# Attenuator_Proto.net
KiCad netlist of a schematic drawn in Altium Designer
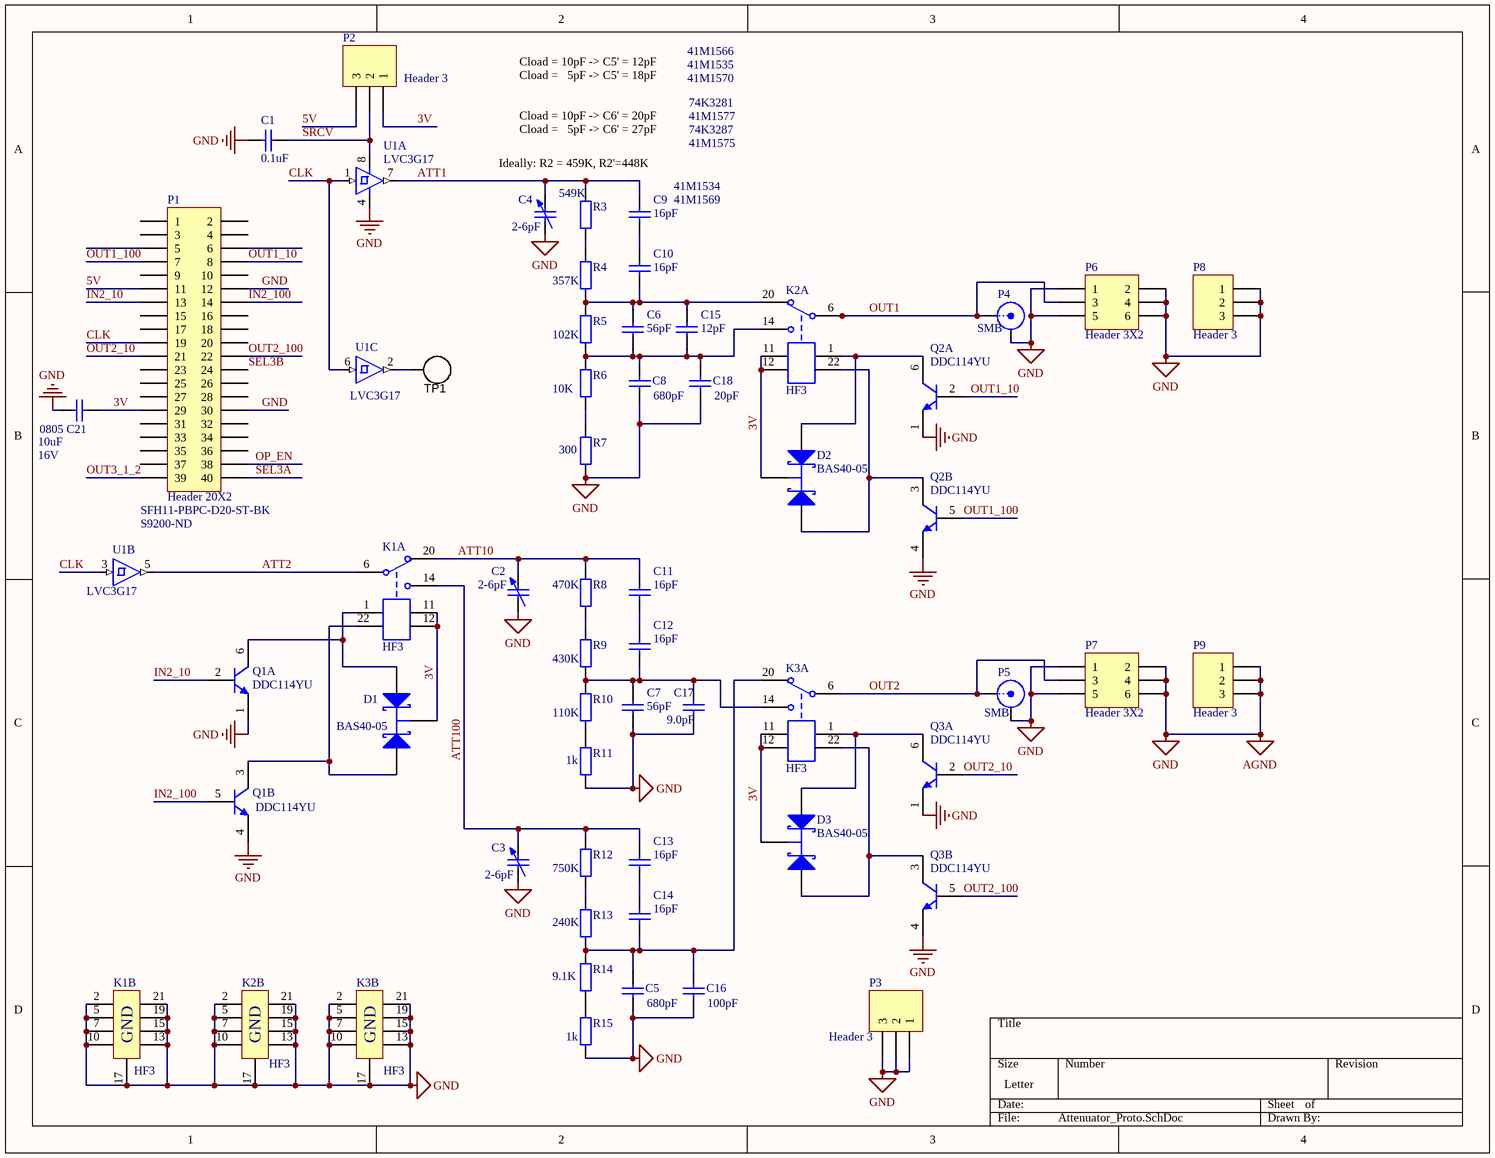
[diagram p0: Attenuator_Proto.SchDoc]

(export (version "E")
  (design (tool "Eeschema 10.0.6"))
  (components
    (comp (ref "C1")
      (value "0.1uF")
      (footprint "C0805")
      (description "Capacitor")
      (fields (field (name "Comment") "Cap") (field (name "PUBLISHER") "Altium Limited"))
      (libsource (lib "Miscellaneous Devices") (part "Cap"))
    )
    (comp (ref "C2")
      (value "2-6pF")
      (footprint "CAPC3225N")
      (description "Variable or Adjustable Capacitor")
      (fields (field (name "Comment") "Cap Var") (field (name "PUBLISHER") "Altium Limited"))
      (libsource (lib "Miscellaneous Devices") (part "Cap Var"))
    )
    (comp (ref "C3")
      (value "2-6pF")
      (footprint "CAPC3225N")
      (description "Variable or Adjustable Capacitor")
      (fields (field (name "Comment") "Cap Var") (field (name "PUBLISHER") "Altium Limited"))
      (libsource (lib "Miscellaneous Devices") (part "Cap Var"))
    )
    (comp (ref "C4")
      (value "2-6pF")
      (footprint "CAPC3225N")
      (description "Variable or Adjustable Capacitor")
      (fields (field (name "Comment") "Cap Var") (field (name "PUBLISHER") "Altium Limited"))
      (libsource (lib "Miscellaneous Devices") (part "Cap Var"))
    )
    (comp (ref "C5")
      (value "680pF")
      (footprint "c0805")
      (description "Capacitor")
      (fields (field (name "Comment") "Cap") (field (name "PUBLISHER") "Altium Limited"))
      (libsource (lib "Miscellaneous Devices") (part "Cap"))
    )
    (comp (ref "C6")
      (value "56pF")
      (footprint "c0805")
      (description "Capacitor")
      (fields (field (name "Comment") "Cap") (field (name "PUBLISHER") "Altium Limited"))
      (libsource (lib "Miscellaneous Devices") (part "Cap"))
    )
    (comp (ref "C7")
      (value "56pF")
      (footprint "c0805")
      (description "Capacitor")
      (fields (field (name "Comment") "Cap") (field (name "PUBLISHER") "Altium Limited"))
      (libsource (lib "Miscellaneous Devices") (part "Cap"))
    )
    (comp (ref "C8")
      (value "680pF")
      (footprint "c0805")
      (description "Capacitor")
      (fields (field (name "Comment") "Cap") (field (name "PUBLISHER") "Altium Limited"))
      (libsource (lib "Miscellaneous Devices") (part "Cap"))
    )
    (comp (ref "C9")
      (value "16pF")
      (footprint "c0805")
      (description "Capacitor")
      (fields
        (field (name "SUPPLIER PART NUMBER 1") "41M1569")
        (field (name "SUPPLIER PART NUMBER 2") "41M1534")
        (field (name "Comment") "Cap")
        (field (name "PUBLISHER") "Altium Limited")
      )
      (libsource (lib "Miscellaneous Devices") (part "Cap"))
    )
    (comp (ref "C10")
      (value "16pF")
      (footprint "c0805")
      (description "Capacitor")
      (fields (field (name "Comment") "Cap") (field (name "PUBLISHER") "Altium Limited"))
      (libsource (lib "Miscellaneous Devices") (part "Cap"))
    )
    (comp (ref "C11")
      (value "16pF")
      (footprint "c0805")
      (description "Capacitor")
      (fields (field (name "Comment") "Cap") (field (name "PUBLISHER") "Altium Limited"))
      (libsource (lib "Miscellaneous Devices") (part "Cap"))
    )
    (comp (ref "C12")
      (value "16pF")
      (footprint "c0805")
      (description "Capacitor")
      (fields (field (name "Comment") "Cap") (field (name "PUBLISHER") "Altium Limited"))
      (libsource (lib "Miscellaneous Devices") (part "Cap"))
    )
    (comp (ref "C13")
      (value "16pF")
      (footprint "c0805")
      (description "Capacitor")
      (fields (field (name "Comment") "Cap") (field (name "PUBLISHER") "Altium Limited"))
      (libsource (lib "Miscellaneous Devices") (part "Cap"))
    )
    (comp (ref "C14")
      (value "16pF")
      (footprint "c0805")
      (description "Capacitor")
      (fields (field (name "Comment") "Cap") (field (name "PUBLISHER") "Altium Limited"))
      (libsource (lib "Miscellaneous Devices") (part "Cap"))
    )
    (comp (ref "C15")
      (value "12pF")
      (footprint "c0805")
      (description "Capacitor")
      (fields
        (field (name "SUPPLIER PART NUMBER 2") "41M1570")
        (field (name "SUPPLIER PART NUMBER 1") "41M1535")
        (field (name "SUPPLIER PART NUMBER 3") "41M1566")
        (field (name "Comment") "Cap")
        (field (name "PUBLISHER") "Altium Limited")
      )
      (libsource (lib "Miscellaneous Devices") (part "Cap"))
    )
    (comp (ref "C16")
      (value "100pF")
      (footprint "c0805")
      (description "Capacitor")
      (fields (field (name "Comment") "Cap") (field (name "PUBLISHER") "Altium Limited"))
      (libsource (lib "Miscellaneous Devices") (part "Cap"))
    )
    (comp (ref "C17")
      (value "9.0pF")
      (footprint "c0805")
      (description "Capacitor")
      (fields (field (name "Comment") "Cap") (field (name "PUBLISHER") "Altium Limited"))
      (libsource (lib "Miscellaneous Devices") (part "Cap"))
    )
    (comp (ref "C18")
      (value "20pF")
      (footprint "c0805")
      (description "Capacitor")
      (fields
        (field (name "SUPPLIER PART NUMBER 1") "41M1575")
        (field (name "SUPPLIER PART NUMBER 2") "74K3287")
        (field (name "SUPPLIER PART NUMBER 3") "41M1577")
        (field (name "SUPPLIER PART NUMBER 4") "74K3281")
        (field (name "Comment") "Cap")
        (field (name "PUBLISHER") "Altium Limited")
      )
      (libsource (lib "Miscellaneous Devices") (part "Cap"))
    )
    (comp (ref "C21")
      (value "10uF")
      (footprint "CAPC2512L")
      (description "Capacitor (Semiconductor SIM Model)")
      (fields
        (field (name "PACKAGEREFERENCE") "0805")
        (field (name "VOLTAGE") "16V")
        (field (name "MANUFACTURER") "Murata")
        (field (name "PARTNUMBER") "GRM21BF51C106ZE15L")
        (field (name "PUBLISHER") "Altium Limited")
      )
      (libsource (lib "Miscellaneous Devices") (part "Cap Semi"))
    )
    (comp (ref "D1")
      (value "BAS40-05")
      (footprint "SOT-23")
      (description "Silicon AF Schottky Diode for High-Speed Switching")
      (fields (field (name "PUBLISHER") "Altium Limited"))
      (libsource (lib "Infineon Discrete Diode") (part "BAS40-05"))
    )
    (comp (ref "D2")
      (value "BAS40-05")
      (footprint "SOT-23")
      (description "Silicon AF Schottky Diode for High-Speed Switching")
      (fields (field (name "PUBLISHER") "Altium Limited"))
      (libsource (lib "Infineon Discrete Diode") (part "BAS40-05"))
    )
    (comp (ref "D3")
      (value "BAS40-05")
      (footprint "SOT-23")
      (description "Silicon AF Schottky Diode for High-Speed Switching")
      (fields (field (name "PUBLISHER") "Altium Limited"))
      (libsource (lib "Infineon Discrete Diode") (part "BAS40-05"))
    )
    (comp (ref "K1")
      (value "HF3_2coils_latching")
      (footprint "HF3-75_Ohm")
      (description "HF3 Relay, Latching type, 2 coils")
      (fields (field (name "MANUFACTURER") "Tyco Electronics") (field (name "PARTNUMBER") "HF3"))
      (libsource (lib "") (part "HF3_2coils_latching_1"))
    )
    (comp (ref "K2")
      (value "HF3_2coils_latching")
      (footprint "HF3-75_Ohm")
      (description "HF3 Relay, Latching type, 2 coils")
      (fields (field (name "MANUFACTURER") "Tyco Electronics") (field (name "PARTNUMBER") "HF3"))
      (libsource (lib "") (part "HF3_2coils_latching_1"))
    )
    (comp (ref "K3")
      (value "HF3_2coils_latching")
      (footprint "HF3-75_Ohm")
      (description "HF3 Relay, Latching type, 2 coils")
      (fields (field (name "MANUFACTURER") "Tyco Electronics") (field (name "PARTNUMBER") "HF3"))
      (libsource (lib "") (part "HF3_2coils_latching_1"))
    )
    (comp (ref "P1")
      (value "Header 20X2")
      (footprint "HDR2X20")
      (description "Header, 20-Pin, Dual row")
      (fields
        (field (name "PARTNUMBER") "SFH11-PBPC-D20-ST-BK")
        (field (name "SUPPLIER PART NUMBER 1") "S9200-ND")
        (field (name "PUBLISHER") "Altium Limited")
      )
      (libsource (lib "Miscellaneous Connectors") (part "Header 20X2"))
    )
    (comp (ref "P2")
      (value "Header 3")
      (footprint "HDR1X3")
      (description "Header, 3-Pin")
      (fields (field (name "PUBLISHER") "Altium Limited"))
      (libsource (lib "Miscellaneous Connectors") (part "Header 3"))
    )
    (comp (ref "P3")
      (value "Header 3")
      (footprint "HDR1X3")
      (description "Header, 3-Pin")
      (fields (field (name "PUBLISHER") "Altium Limited"))
      (libsource (lib "") (part "Header 3_2"))
    )
    (comp (ref "P4")
      (value "SMB")
      (footprint "SMB_V-RJ45")
      (description "SMB Straight Connector")
      (fields (field (name "PUBLISHER") "Altium Limited"))
      (libsource (lib "Miscellaneous Connectors") (part "SMB"))
    )
    (comp (ref "P5")
      (value "SMB")
      (footprint "SMB_V-RJ45")
      (description "SMB Straight Connector")
      (fields (field (name "PUBLISHER") "Altium Limited"))
      (libsource (lib "Miscellaneous Connectors") (part "SMB"))
    )
    (comp (ref "P6")
      (value "Header 3X2")
      (footprint "HDR2X3")
      (description "Header, 3-Pin, Dual row")
      (fields (field (name "PUBLISHER") "Altium Limited"))
      (libsource (lib "Miscellaneous Connectors") (part "Header 3X2"))
    )
    (comp (ref "P7")
      (value "Header 3X2")
      (footprint "HDR2X3")
      (description "Header, 3-Pin, Dual row")
      (fields (field (name "PUBLISHER") "Altium Limited"))
      (libsource (lib "Miscellaneous Connectors") (part "Header 3X2"))
    )
    (comp (ref "P8")
      (value "Header 3")
      (footprint "HDR1X3")
      (description "Header, 3-Pin")
      (fields (field (name "PUBLISHER") "Altium Limited"))
      (libsource (lib "") (part "Header 3_1"))
    )
    (comp (ref "P9")
      (value "Header 3")
      (footprint "HDR1X3")
      (description "Header, 3-Pin")
      (fields (field (name "PUBLISHER") "Altium Limited"))
      (libsource (lib "") (part "Header 3_1"))
    )
    (comp (ref "Q1")
      (value "DDCxxxxU")
      (footprint "SOT-363")
      (description "NPN PRE-BIASED SMALL SIGNAL DUAL SURFACE MOUNT TRANSISTOR")
      (fields (field (name "PARTNUMBER") "DDC114YU"))
      (libsource (lib "iXBT") (part "DDCxxxxU"))
    )
    (comp (ref "Q2")
      (value "DDCxxxxU")
      (footprint "SOT-363")
      (description "NPN PRE-BIASED SMALL SIGNAL DUAL SURFACE MOUNT TRANSISTOR")
      (fields (field (name "PARTNUMBER") "DDC114YU"))
      (libsource (lib "iXBT") (part "DDCxxxxU"))
    )
    (comp (ref "Q3")
      (value "DDCxxxxU")
      (footprint "SOT-363")
      (description "NPN PRE-BIASED SMALL SIGNAL DUAL SURFACE MOUNT TRANSISTOR")
      (fields (field (name "PARTNUMBER") "DDC114YU"))
      (libsource (lib "iXBT") (part "DDCxxxxU"))
    )
    (comp (ref "R3")
      (value "549K")
      (footprint "0805")
      (description "Resistor")
      (fields (field (name "Comment") "Res2") (field (name "PUBLISHER") "Altium Limited"))
      (libsource (lib "Miscellaneous Devices") (part "Res2"))
    )
    (comp (ref "R4")
      (value "357K")
      (footprint "0805")
      (description "Resistor")
      (fields (field (name "Comment") "Res2") (field (name "PUBLISHER") "Altium Limited"))
      (libsource (lib "Miscellaneous Devices") (part "Res2"))
    )
    (comp (ref "R5")
      (value "102K")
      (footprint "0805")
      (description "Resistor")
      (fields (field (name "Comment") "Res2") (field (name "PUBLISHER") "Altium Limited"))
      (libsource (lib "Miscellaneous Devices") (part "Res2"))
    )
    (comp (ref "R6")
      (value "10K")
      (footprint "0805")
      (description "Resistor")
      (fields (field (name "Comment") "Res2") (field (name "PUBLISHER") "Altium Limited"))
      (libsource (lib "Miscellaneous Devices") (part "Res2"))
    )
    (comp (ref "R7")
      (value "300")
      (footprint "0805")
      (description "Resistor")
      (fields (field (name "Comment") "Res2") (field (name "PUBLISHER") "Altium Limited"))
      (libsource (lib "Miscellaneous Devices") (part "Res2"))
    )
    (comp (ref "R8")
      (value "470K")
      (footprint "0805")
      (description "Resistor")
      (fields (field (name "Comment") "Res2") (field (name "PUBLISHER") "Altium Limited"))
      (libsource (lib "Miscellaneous Devices") (part "Res2"))
    )
    (comp (ref "R9")
      (value "430K")
      (footprint "0805")
      (description "Resistor")
      (fields (field (name "Comment") "Res2") (field (name "PUBLISHER") "Altium Limited"))
      (libsource (lib "Miscellaneous Devices") (part "Res2"))
    )
    (comp (ref "R10")
      (value "110K")
      (footprint "0805")
      (description "Resistor")
      (fields (field (name "Comment") "Res2") (field (name "PUBLISHER") "Altium Limited"))
      (libsource (lib "Miscellaneous Devices") (part "Res2"))
    )
    (comp (ref "R11")
      (value "1k")
      (footprint "0805")
      (description "Resistor")
      (fields (field (name "Comment") "Res2") (field (name "PUBLISHER") "Altium Limited"))
      (libsource (lib "Miscellaneous Devices") (part "Res2"))
    )
    (comp (ref "R12")
      (value "750K")
      (footprint "0805")
      (description "Resistor")
      (fields (field (name "Comment") "Res2") (field (name "PUBLISHER") "Altium Limited"))
      (libsource (lib "Miscellaneous Devices") (part "Res2"))
    )
    (comp (ref "R13")
      (value "240K")
      (footprint "0805")
      (description "Resistor")
      (fields (field (name "Comment") "Res2") (field (name "PUBLISHER") "Altium Limited"))
      (libsource (lib "Miscellaneous Devices") (part "Res2"))
    )
    (comp (ref "R14")
      (value "9.1K")
      (footprint "0805")
      (description "Resistor")
      (fields (field (name "Comment") "Res2") (field (name "PUBLISHER") "Altium Limited"))
      (libsource (lib "Miscellaneous Devices") (part "Res2"))
    )
    (comp (ref "R15")
      (value "1k")
      (footprint "0805")
      (description "Resistor")
      (fields (field (name "Comment") "Res2") (field (name "PUBLISHER") "Altium Limited"))
      (libsource (lib "Miscellaneous Devices") (part "Res2"))
    )
    (comp (ref "TP1")
      (value "TESTPOINT")
      (footprint "TESTPOINT")
      (description "TEST POINT.  No entry in BOM.")
      (libsource (lib "NSC MiscParts") (part "TESTPOINT"))
    )
    (comp (ref "U1")
      (value "LVC3G17")
      (footprint "sm8")
      (fields
        (field (name "MANUFACTURER") "Texas Instruments")
        (field (name "MANUFACTURER PART NUMBER") "SN74LVC3G17DCTR")
      )
      (libsource (lib "VIVENG_Library") (part "SN74LVC3G17DCTR"))
    )
  )
  (nets
    (net (code "1") (name "/3V") (class "Default")
      (node (ref "C21") (pin "1") (pinfunction "1_1") (pintype "passive"))
      (node (ref "D1") (pin "3") (pinfunction "K_3") (pintype "passive"))
      (node (ref "D2") (pin "3") (pinfunction "K_3") (pintype "passive"))
      (node (ref "D3") (pin "3") (pinfunction "K_3") (pintype "passive"))
      (node (ref "K1") (pin "11") (pinfunction "11_11") (pintype "passive"))
      (node (ref "K1") (pin "12") (pinfunction "12_12") (pintype "passive"))
      (node (ref "K2") (pin "11") (pinfunction "11_11") (pintype "passive"))
      (node (ref "K2") (pin "12") (pinfunction "12_12") (pintype "passive"))
      (node (ref "K3") (pin "11") (pinfunction "11_11") (pintype "passive"))
      (node (ref "K3") (pin "12") (pinfunction "12_12") (pintype "passive"))
      (node (ref "P1") (pin "29") (pinfunction "29_29") (pintype "passive"))
      (node (ref "P2") (pin "1") (pinfunction "1_1") (pintype "passive"))
    )
    (net (code "2") (name "/5V") (class "Default")
      (node (ref "P1") (pin "11") (pinfunction "11_11") (pintype "passive"))
      (node (ref "P2") (pin "3") (pinfunction "3_3") (pintype "passive"))
    )
    (net (code "3") (name "/ATT1") (class "Default")
      (node (ref "C4") (pin "2") (pinfunction "2_2") (pintype "passive"))
      (node (ref "C9") (pin "2") (pinfunction "2_2") (pintype "passive"))
      (node (ref "R3") (pin "2") (pinfunction "2_2") (pintype "passive"))
      (node (ref "U1") (pin "7") (pinfunction "1Y_7") (pintype "output"))
    )
    (net (code "4") (name "/ATT2") (class "Default")
      (node (ref "K1") (pin "6") (pinfunction "6_6") (pintype "passive"))
      (node (ref "U1") (pin "5") (pinfunction "2Y_5") (pintype "output"))
    )
    (net (code "5") (name "/ATT10") (class "Default")
      (node (ref "C11") (pin "2") (pinfunction "2_2") (pintype "passive"))
      (node (ref "C2") (pin "2") (pinfunction "2_2") (pintype "passive"))
      (node (ref "K1") (pin "20") (pinfunction "20_20") (pintype "passive"))
      (node (ref "R8") (pin "2") (pinfunction "2_2") (pintype "passive"))
    )
    (net (code "6") (name "/ATT100") (class "Default")
      (node (ref "C13") (pin "2") (pinfunction "2_2") (pintype "passive"))
      (node (ref "C3") (pin "2") (pinfunction "2_2") (pintype "passive"))
      (node (ref "K1") (pin "14") (pinfunction "14_14") (pintype "passive"))
      (node (ref "R12") (pin "2") (pinfunction "2_2") (pintype "passive"))
    )
    (net (code "7") (name "/CLK") (class "Default")
      (node (ref "P1") (pin "19") (pinfunction "19_19") (pintype "passive"))
      (node (ref "U1") (pin "1") (pinfunction "1A_1") (pintype "input"))
      (node (ref "U1") (pin "3") (pinfunction "2A_3") (pintype "input"))
      (node (ref "U1") (pin "6") (pinfunction "3A_6") (pintype "input"))
    )
    (net (code "8") (name "/IN2_10") (class "Default")
      (node (ref "P1") (pin "13") (pinfunction "13_13") (pintype "passive"))
      (node (ref "Q1") (pin "2") (pinfunction "B_2") (pintype "passive"))
    )
    (net (code "9") (name "/IN2_100") (class "Default")
      (node (ref "P1") (pin "14") (pinfunction "14_14") (pintype "passive"))
      (node (ref "Q1") (pin "5") (pinfunction "B_5") (pintype "passive"))
    )
    (net (code "10") (name "/OP_EN") (class "Default")
      (node (ref "P1") (pin "38") (pinfunction "38_38") (pintype "passive"))
    )
    (net (code "11") (name "/OUT1") (class "Default")
      (node (ref "K2") (pin "6") (pinfunction "6_6") (pintype "passive"))
      (node (ref "P4") (pin "1") (pinfunction "X_1") (pintype "passive"))
      (node (ref "P6") (pin "3") (pinfunction "3_3") (pintype "passive"))
    )
    (net (code "12") (name "/OUT1_10") (class "Default")
      (node (ref "P1") (pin "8") (pinfunction "8_8") (pintype "passive"))
      (node (ref "Q2") (pin "2") (pinfunction "B_2") (pintype "passive"))
    )
    (net (code "13") (name "/OUT1_100") (class "Default")
      (node (ref "P1") (pin "7") (pinfunction "7_7") (pintype "passive"))
      (node (ref "Q2") (pin "5") (pinfunction "B_5") (pintype "passive"))
    )
    (net (code "14") (name "/OUT2") (class "Default")
      (node (ref "K3") (pin "6") (pinfunction "6_6") (pintype "passive"))
      (node (ref "P5") (pin "1") (pinfunction "X_1") (pintype "passive"))
      (node (ref "P7") (pin "3") (pinfunction "3_3") (pintype "passive"))
    )
    (net (code "15") (name "/OUT2_10") (class "Default")
      (node (ref "P1") (pin "21") (pinfunction "21_21") (pintype "passive"))
      (node (ref "Q3") (pin "2") (pinfunction "B_2") (pintype "passive"))
    )
    (net (code "16") (name "/OUT2_100") (class "Default")
      (node (ref "P1") (pin "22") (pinfunction "22_22") (pintype "passive"))
      (node (ref "Q3") (pin "5") (pinfunction "B_5") (pintype "passive"))
    )
    (net (code "17") (name "/OUT3_1_2") (class "Default")
      (node (ref "P1") (pin "39") (pinfunction "39_39") (pintype "passive"))
    )
    (net (code "18") (name "/SEL3A") (class "Default")
      (node (ref "P1") (pin "40") (pinfunction "40_40") (pintype "passive"))
    )
    (net (code "19") (name "/SEL3B") (class "Default")
      (node (ref "P1") (pin "24") (pinfunction "24_24") (pintype "passive"))
    )
    (net (code "20") (name "/SRCV") (class "Default")
      (node (ref "C1") (pin "1") (pinfunction "1_1") (pintype "passive"))
      (node (ref "P2") (pin "2") (pinfunction "2_2") (pintype "passive"))
      (node (ref "U1") (pin "8") (pinfunction "VCC_8") (pintype "power_in"))
    )
    (net (code "21") (name "AGND") (class "Default")
      (node (ref "C1") (pin "2") (pinfunction "2_2") (pintype "passive"))
      (node (ref "C16") (pin "1") (pinfunction "1_1") (pintype "passive"))
      (node (ref "C17") (pin "1") (pinfunction "1_1") (pintype "passive"))
      (node (ref "C18") (pin "1") (pinfunction "1_1") (pintype "passive"))
      (node (ref "C2") (pin "1") (pinfunction "1_1") (pintype "passive"))
      (node (ref "C21") (pin "2") (pinfunction "2_2") (pintype "passive"))
      (node (ref "C3") (pin "1") (pinfunction "1_1") (pintype "passive"))
      (node (ref "C4") (pin "1") (pinfunction "1_1") (pintype "passive"))
      (node (ref "C5") (pin "1") (pinfunction "1_1") (pintype "passive"))
      (node (ref "C7") (pin "1") (pinfunction "1_1") (pintype "passive"))
      (node (ref "C8") (pin "1") (pinfunction "1_1") (pintype "passive"))
      (node (ref "K1") (pin "10") (pinfunction "GND_10") (pintype "power_in"))
      (node (ref "K1") (pin "13") (pinfunction "GND_13") (pintype "power_in"))
      (node (ref "K1") (pin "15") (pinfunction "GND_15") (pintype "power_in"))
      (node (ref "K1") (pin "17") (pinfunction "GND_17") (pintype "power_in"))
      (node (ref "K1") (pin "19") (pinfunction "GND_19") (pintype "power_in"))
      (node (ref "K1") (pin "2") (pinfunction "GND_2") (pintype "power_in"))
      (node (ref "K1") (pin "21") (pinfunction "GND_21") (pintype "power_in"))
      (node (ref "K1") (pin "5") (pinfunction "GND_5") (pintype "power_in"))
      (node (ref "K1") (pin "7") (pinfunction "GND_7") (pintype "power_in"))
      (node (ref "K2") (pin "10") (pinfunction "GND_10") (pintype "power_in"))
      (node (ref "K2") (pin "13") (pinfunction "GND_13") (pintype "power_in"))
      (node (ref "K2") (pin "15") (pinfunction "GND_15") (pintype "power_in"))
      (node (ref "K2") (pin "17") (pinfunction "GND_17") (pintype "power_in"))
      (node (ref "K2") (pin "19") (pinfunction "GND_19") (pintype "power_in"))
      (node (ref "K2") (pin "2") (pinfunction "GND_2") (pintype "power_in"))
      (node (ref "K2") (pin "21") (pinfunction "GND_21") (pintype "power_in"))
      (node (ref "K2") (pin "5") (pinfunction "GND_5") (pintype "power_in"))
      (node (ref "K2") (pin "7") (pinfunction "GND_7") (pintype "power_in"))
      (node (ref "K3") (pin "10") (pinfunction "GND_10") (pintype "power_in"))
      (node (ref "K3") (pin "13") (pinfunction "GND_13") (pintype "power_in"))
      (node (ref "K3") (pin "15") (pinfunction "GND_15") (pintype "power_in"))
      (node (ref "K3") (pin "17") (pinfunction "GND_17") (pintype "power_in"))
      (node (ref "K3") (pin "19") (pinfunction "GND_19") (pintype "power_in"))
      (node (ref "K3") (pin "2") (pinfunction "GND_2") (pintype "power_in"))
      (node (ref "K3") (pin "21") (pinfunction "GND_21") (pintype "power_in"))
      (node (ref "K3") (pin "5") (pinfunction "GND_5") (pintype "power_in"))
      (node (ref "K3") (pin "7") (pinfunction "GND_7") (pintype "power_in"))
      (node (ref "P1") (pin "12") (pinfunction "12_12") (pintype "passive"))
      (node (ref "P1") (pin "30") (pinfunction "30_30") (pintype "passive"))
      (node (ref "P3") (pin "1") (pinfunction "1_1") (pintype "passive"))
      (node (ref "P3") (pin "2") (pinfunction "2_2") (pintype "passive"))
      (node (ref "P3") (pin "3") (pinfunction "3_3") (pintype "passive"))
      (node (ref "P4") (pin "2") (pinfunction "Y_2") (pintype "passive"))
      (node (ref "P5") (pin "2") (pinfunction "Y_2") (pintype "passive"))
      (node (ref "P6") (pin "1") (pinfunction "1_1") (pintype "passive"))
      (node (ref "P6") (pin "2") (pinfunction "2_2") (pintype "passive"))
      (node (ref "P6") (pin "4") (pinfunction "4_4") (pintype "passive"))
      (node (ref "P6") (pin "5") (pinfunction "5_5") (pintype "passive"))
      (node (ref "P6") (pin "6") (pinfunction "6_6") (pintype "passive"))
      (node (ref "P7") (pin "1") (pinfunction "1_1") (pintype "passive"))
      (node (ref "P7") (pin "2") (pinfunction "2_2") (pintype "passive"))
      (node (ref "P7") (pin "4") (pinfunction "4_4") (pintype "passive"))
      (node (ref "P7") (pin "5") (pinfunction "5_5") (pintype "passive"))
      (node (ref "P7") (pin "6") (pinfunction "6_6") (pintype "passive"))
      (node (ref "P8") (pin "1") (pinfunction "1_1") (pintype "passive"))
      (node (ref "P8") (pin "2") (pinfunction "2_2") (pintype "passive"))
      (node (ref "P8") (pin "3") (pinfunction "3_3") (pintype "passive"))
      (node (ref "P9") (pin "1") (pinfunction "1_1") (pintype "passive"))
      (node (ref "P9") (pin "2") (pinfunction "2_2") (pintype "passive"))
      (node (ref "P9") (pin "3") (pinfunction "3_3") (pintype "passive"))
      (node (ref "Q1") (pin "1") (pinfunction "E_1") (pintype "passive"))
      (node (ref "Q1") (pin "4") (pinfunction "E_4") (pintype "passive"))
      (node (ref "Q2") (pin "1") (pinfunction "E_1") (pintype "passive"))
      (node (ref "Q2") (pin "4") (pinfunction "E_4") (pintype "passive"))
      (node (ref "Q3") (pin "1") (pinfunction "E_1") (pintype "passive"))
      (node (ref "Q3") (pin "4") (pinfunction "E_4") (pintype "passive"))
      (node (ref "R11") (pin "1") (pinfunction "1_1") (pintype "passive"))
      (node (ref "R15") (pin "1") (pinfunction "1_1") (pintype "passive"))
      (node (ref "R7") (pin "1") (pinfunction "1_1") (pintype "passive"))
      (node (ref "U1") (pin "4") (pinfunction "GND_4") (pintype "power_in"))
    )
    (net (code "22") (name "Net-(C10-Pad1)") (class "Default")
      (node (ref "C10") (pin "1") (pinfunction "1_1") (pintype "passive"))
      (node (ref "C15") (pin "2") (pinfunction "2_2") (pintype "passive"))
      (node (ref "C6") (pin "2") (pinfunction "2_2") (pintype "passive"))
      (node (ref "K2") (pin "20") (pinfunction "20_20") (pintype "passive"))
      (node (ref "R4") (pin "1") (pinfunction "1_1") (pintype "passive"))
      (node (ref "R5") (pin "2") (pinfunction "2_2") (pintype "passive"))
    )
    (net (code "23") (name "Net-(C10-Pad2)") (class "Default")
      (node (ref "C10") (pin "2") (pinfunction "2_2") (pintype "passive"))
      (node (ref "C9") (pin "1") (pinfunction "1_1") (pintype "passive"))
    )
    (net (code "24") (name "Net-(C11-Pad1)") (class "Default")
      (node (ref "C11") (pin "1") (pinfunction "1_1") (pintype "passive"))
      (node (ref "C12") (pin "2") (pinfunction "2_2") (pintype "passive"))
    )
    (net (code "25") (name "Net-(C12-Pad1)") (class "Default")
      (node (ref "C12") (pin "1") (pinfunction "1_1") (pintype "passive"))
      (node (ref "C17") (pin "2") (pinfunction "2_2") (pintype "passive"))
      (node (ref "C7") (pin "2") (pinfunction "2_2") (pintype "passive"))
      (node (ref "K3") (pin "14") (pinfunction "14_14") (pintype "passive"))
      (node (ref "R10") (pin "2") (pinfunction "2_2") (pintype "passive"))
      (node (ref "R9") (pin "1") (pinfunction "1_1") (pintype "passive"))
    )
    (net (code "26") (name "Net-(C13-Pad1)") (class "Default")
      (node (ref "C13") (pin "1") (pinfunction "1_1") (pintype "passive"))
      (node (ref "C14") (pin "2") (pinfunction "2_2") (pintype "passive"))
    )
    (net (code "27") (name "Net-(C14-Pad1)") (class "Default")
      (node (ref "C14") (pin "1") (pinfunction "1_1") (pintype "passive"))
      (node (ref "C16") (pin "2") (pinfunction "2_2") (pintype "passive"))
      (node (ref "C5") (pin "2") (pinfunction "2_2") (pintype "passive"))
      (node (ref "K3") (pin "20") (pinfunction "20_20") (pintype "passive"))
      (node (ref "R13") (pin "1") (pinfunction "1_1") (pintype "passive"))
      (node (ref "R14") (pin "2") (pinfunction "2_2") (pintype "passive"))
    )
    (net (code "28") (name "Net-(C15-Pad1)") (class "Default")
      (node (ref "C15") (pin "1") (pinfunction "1_1") (pintype "passive"))
      (node (ref "C18") (pin "2") (pinfunction "2_2") (pintype "passive"))
      (node (ref "C6") (pin "1") (pinfunction "1_1") (pintype "passive"))
      (node (ref "C8") (pin "2") (pinfunction "2_2") (pintype "passive"))
      (node (ref "K2") (pin "14") (pinfunction "14_14") (pintype "passive"))
      (node (ref "R5") (pin "1") (pinfunction "1_1") (pintype "passive"))
      (node (ref "R6") (pin "2") (pinfunction "2_2") (pintype "passive"))
    )
    (net (code "29") (name "Net-(D1-A1)") (class "Default")
      (node (ref "D1") (pin "1") (pinfunction "A1_1") (pintype "passive"))
      (node (ref "K1") (pin "1") (pinfunction "1_1") (pintype "passive"))
      (node (ref "Q1") (pin "6") (pinfunction "C_6") (pintype "passive"))
    )
    (net (code "30") (name "Net-(D1-A2)") (class "Default")
      (node (ref "D1") (pin "2") (pinfunction "A2_2") (pintype "passive"))
      (node (ref "K1") (pin "22") (pinfunction "22_22") (pintype "passive"))
      (node (ref "Q1") (pin "3") (pinfunction "C_3") (pintype "passive"))
    )
    (net (code "31") (name "Net-(D2-A1)") (class "Default")
      (node (ref "D2") (pin "1") (pinfunction "A1_1") (pintype "passive"))
      (node (ref "K2") (pin "1") (pinfunction "1_1") (pintype "passive"))
      (node (ref "Q2") (pin "6") (pinfunction "C_6") (pintype "passive"))
    )
    (net (code "32") (name "Net-(D2-A2)") (class "Default")
      (node (ref "D2") (pin "2") (pinfunction "A2_2") (pintype "passive"))
      (node (ref "K2") (pin "22") (pinfunction "22_22") (pintype "passive"))
      (node (ref "Q2") (pin "3") (pinfunction "C_3") (pintype "passive"))
    )
    (net (code "33") (name "Net-(D3-A1)") (class "Default")
      (node (ref "D3") (pin "1") (pinfunction "A1_1") (pintype "passive"))
      (node (ref "K3") (pin "1") (pinfunction "1_1") (pintype "passive"))
      (node (ref "Q3") (pin "6") (pinfunction "C_6") (pintype "passive"))
    )
    (net (code "34") (name "Net-(D3-A2)") (class "Default")
      (node (ref "D3") (pin "2") (pinfunction "A2_2") (pintype "passive"))
      (node (ref "K3") (pin "22") (pinfunction "22_22") (pintype "passive"))
      (node (ref "Q3") (pin "3") (pinfunction "C_3") (pintype "passive"))
    )
    (net (code "35") (name "Net-(R3-Pad1)") (class "Default")
      (node (ref "R3") (pin "1") (pinfunction "1_1") (pintype "passive"))
      (node (ref "R4") (pin "2") (pinfunction "2_2") (pintype "passive"))
    )
    (net (code "36") (name "Net-(R6-Pad1)") (class "Default")
      (node (ref "R6") (pin "1") (pinfunction "1_1") (pintype "passive"))
      (node (ref "R7") (pin "2") (pinfunction "2_2") (pintype "passive"))
    )
    (net (code "37") (name "Net-(R8-Pad1)") (class "Default")
      (node (ref "R8") (pin "1") (pinfunction "1_1") (pintype "passive"))
      (node (ref "R9") (pin "2") (pinfunction "2_2") (pintype "passive"))
    )
    (net (code "38") (name "Net-(R10-Pad1)") (class "Default")
      (node (ref "R10") (pin "1") (pinfunction "1_1") (pintype "passive"))
      (node (ref "R11") (pin "2") (pinfunction "2_2") (pintype "passive"))
    )
    (net (code "39") (name "Net-(R12-Pad1)") (class "Default")
      (node (ref "R12") (pin "1") (pinfunction "1_1") (pintype "passive"))
      (node (ref "R13") (pin "2") (pinfunction "2_2") (pintype "passive"))
    )
    (net (code "40") (name "Net-(R14-Pad1)") (class "Default")
      (node (ref "R14") (pin "1") (pinfunction "1_1") (pintype "passive"))
      (node (ref "R15") (pin "2") (pinfunction "2_2") (pintype "passive"))
    )
    (net (code "41") (name "Net-(U1C-3Y)") (class "Default")
      (node (ref "TP1") (pin "1") (pintype "passive"))
      (node (ref "U1") (pin "2") (pinfunction "3Y_2") (pintype "output"))
    )
    (net (code "42") (name "unconnected-(P1-Pad1)") (class "Default")
      (node (ref "P1") (pin "1") (pinfunction "1_1") (pintype "passive"))
    )
    (net (code "43") (name "unconnected-(P1-Pad2)") (class "Default")
      (node (ref "P1") (pin "2") (pinfunction "2_2") (pintype "passive"))
    )
    (net (code "44") (name "unconnected-(P1-Pad3)") (class "Default")
      (node (ref "P1") (pin "3") (pinfunction "3_3") (pintype "passive"))
    )
    (net (code "45") (name "unconnected-(P1-Pad4)") (class "Default")
      (node (ref "P1") (pin "4") (pinfunction "4_4") (pintype "passive"))
    )
    (net (code "46") (name "unconnected-(P1-Pad5)") (class "Default")
      (node (ref "P1") (pin "5") (pinfunction "5_5") (pintype "passive"))
    )
    (net (code "47") (name "unconnected-(P1-Pad6)") (class "Default")
      (node (ref "P1") (pin "6") (pinfunction "6_6") (pintype "passive"))
    )
    (net (code "48") (name "unconnected-(P1-Pad9)") (class "Default")
      (node (ref "P1") (pin "9") (pinfunction "9_9") (pintype "passive"))
    )
    (net (code "49") (name "unconnected-(P1-Pad10)") (class "Default")
      (node (ref "P1") (pin "10") (pinfunction "10_10") (pintype "passive"))
    )
    (net (code "50") (name "unconnected-(P1-Pad15)") (class "Default")
      (node (ref "P1") (pin "15") (pinfunction "15_15") (pintype "passive"))
    )
    (net (code "51") (name "unconnected-(P1-Pad16)") (class "Default")
      (node (ref "P1") (pin "16") (pinfunction "16_16") (pintype "passive"))
    )
    (net (code "52") (name "unconnected-(P1-Pad17)") (class "Default")
      (node (ref "P1") (pin "17") (pinfunction "17_17") (pintype "passive"))
    )
    (net (code "53") (name "unconnected-(P1-Pad18)") (class "Default")
      (node (ref "P1") (pin "18") (pinfunction "18_18") (pintype "passive"))
    )
    (net (code "54") (name "unconnected-(P1-Pad20)") (class "Default")
      (node (ref "P1") (pin "20") (pinfunction "20_20") (pintype "passive"))
    )
    (net (code "55") (name "unconnected-(P1-Pad23)") (class "Default")
      (node (ref "P1") (pin "23") (pinfunction "23_23") (pintype "passive"))
    )
    (net (code "56") (name "unconnected-(P1-Pad25)") (class "Default")
      (node (ref "P1") (pin "25") (pinfunction "25_25") (pintype "passive"))
    )
    (net (code "57") (name "unconnected-(P1-Pad26)") (class "Default")
      (node (ref "P1") (pin "26") (pinfunction "26_26") (pintype "passive"))
    )
    (net (code "58") (name "unconnected-(P1-Pad27)") (class "Default")
      (node (ref "P1") (pin "27") (pinfunction "27_27") (pintype "passive"))
    )
    (net (code "59") (name "unconnected-(P1-Pad28)") (class "Default")
      (node (ref "P1") (pin "28") (pinfunction "28_28") (pintype "passive"))
    )
    (net (code "60") (name "unconnected-(P1-Pad31)") (class "Default")
      (node (ref "P1") (pin "31") (pinfunction "31_31") (pintype "passive"))
    )
    (net (code "61") (name "unconnected-(P1-Pad32)") (class "Default")
      (node (ref "P1") (pin "32") (pinfunction "32_32") (pintype "passive"))
    )
    (net (code "62") (name "unconnected-(P1-Pad33)") (class "Default")
      (node (ref "P1") (pin "33") (pinfunction "33_33") (pintype "passive"))
    )
    (net (code "63") (name "unconnected-(P1-Pad34)") (class "Default")
      (node (ref "P1") (pin "34") (pinfunction "34_34") (pintype "passive"))
    )
    (net (code "64") (name "unconnected-(P1-Pad35)") (class "Default")
      (node (ref "P1") (pin "35") (pinfunction "35_35") (pintype "passive"))
    )
    (net (code "65") (name "unconnected-(P1-Pad36)") (class "Default")
      (node (ref "P1") (pin "36") (pinfunction "36_36") (pintype "passive"))
    )
    (net (code "66") (name "unconnected-(P1-Pad37)") (class "Default")
      (node (ref "P1") (pin "37") (pinfunction "37_37") (pintype "passive"))
    )
  )
)
